# nerves_key4.net
KiCad netlist of a schematic drawn in EAGLE
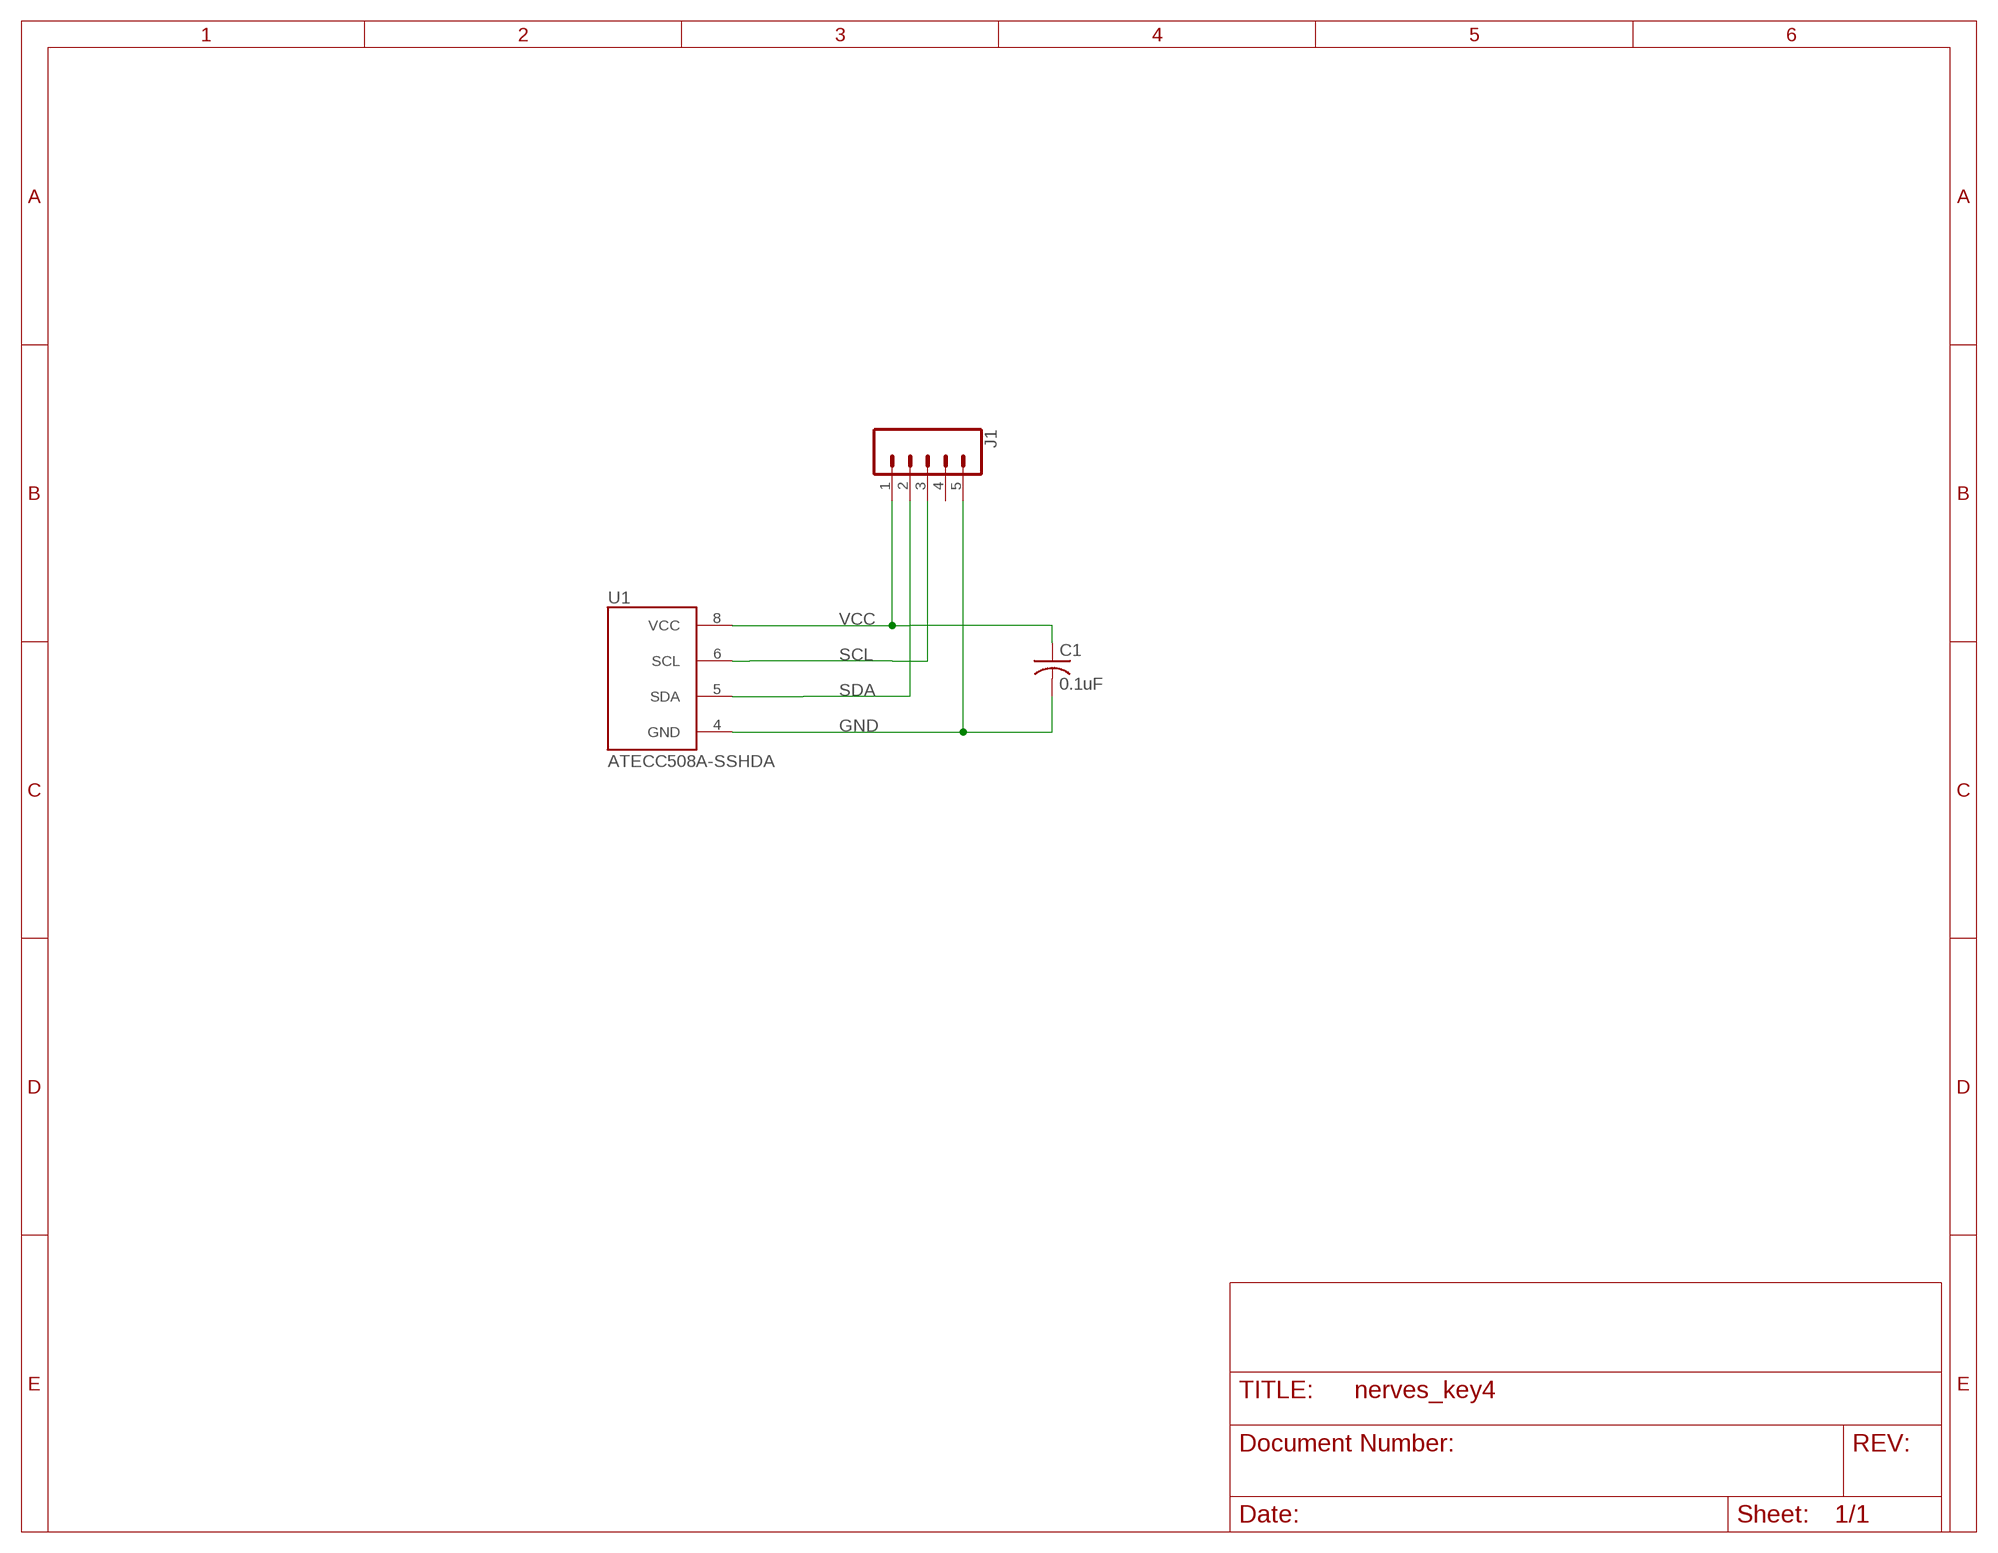
[diagram p0: schematic, sheet 1]

(export (version "E")
  (design (tool "Eeschema 10.0.6"))
  (components
    (comp (ref "C1")
      (value "0.1uF")
      (footprint "eagle-import:C0603")
      (libsource (lib "eagle-import") (part "C-USC0603"))
    )
    (comp (ref "J1")
      (value "CONN_05")
      (footprint "eagle-import:1X05")
      (libsource (lib "eagle-import") (part "CONN_05"))
    )
    (comp (ref "U1")
      (value "ATECC508A-SSHDA")
      (footprint "eagle-import:SOIC127P625X175-8")
      (libsource (lib "eagle-import") (part "ATECC508ASOIC-8-NARROW"))
    )
  )
  (nets
    (net (code "1") (name "/GND") (class "Default")
      (node (ref "C1") (pin "2") (pinfunction "2_2") (pintype "passive"))
      (node (ref "J1") (pin "5") (pinfunction "5_5") (pintype "passive"))
      (node (ref "U1") (pin "4") (pinfunction "GND_4") (pintype "bidirectional"))
    )
    (net (code "2") (name "/SCL") (class "Default")
      (node (ref "J1") (pin "3") (pinfunction "3_3") (pintype "passive"))
      (node (ref "U1") (pin "6") (pinfunction "SCL_6") (pintype "bidirectional"))
    )
    (net (code "3") (name "/SDA") (class "Default")
      (node (ref "J1") (pin "2") (pinfunction "2_2") (pintype "passive"))
      (node (ref "U1") (pin "5") (pinfunction "SDA_5") (pintype "bidirectional"))
    )
    (net (code "4") (name "/VCC") (class "Default")
      (node (ref "C1") (pin "1") (pinfunction "1_1") (pintype "passive"))
      (node (ref "J1") (pin "1") (pinfunction "1_1") (pintype "passive"))
      (node (ref "U1") (pin "8") (pinfunction "VCC_8") (pintype "bidirectional"))
    )
    (net (code "5") (name "unconnected-(J1-Pad4)") (class "Default")
      (node (ref "J1") (pin "4") (pinfunction "4_4") (pintype "passive"))
    )
  )
)
